# CAN_Interface.net
KiCad netlist of a schematic drawn in Altium Designer
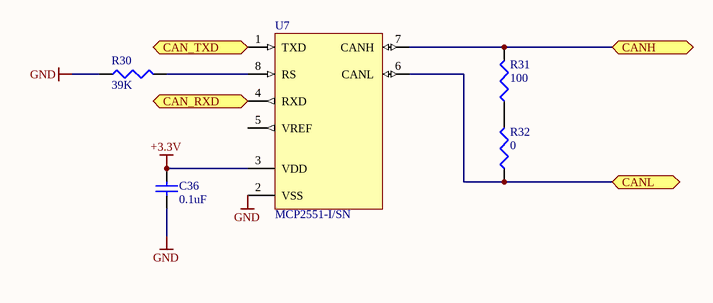
[diagram p0: CAN Interface.SchDoc]

(export (version "E")
  (design (tool "Eeschema 10.0.6"))
  (components
    (comp (ref "C36")
      (value "0.1uF")
      (footprint "2012[0805]")
      (description "Ceramic Chip Capacitor - Standard")
      (fields (field (name "PUBLISHER") "Altium Limited"))
      (libsource (lib "ResAndCaps") (part "C0805"))
    )
    (comp (ref "R30")
      (value "39K")
      (footprint "R2012[0805]")
      (description "R0805")
      (fields (field (name "PUBLISHER") "Altium Limited"))
      (libsource (lib "ResAndCaps") (part "R0805"))
    )
    (comp (ref "R31")
      (value "100")
      (footprint "R2012[0805]")
      (description "R0805")
      (fields (field (name "PUBLISHER") "Altium Limited"))
      (libsource (lib "ResAndCaps") (part "R0805"))
    )
    (comp (ref "R32")
      (value "0")
      (footprint "R2012[0805]")
      (description "R0805")
      (fields (field (name "PUBLISHER") "Altium Limited"))
      (libsource (lib "ResAndCaps") (part "R0805"))
    )
    (comp (ref "U7")
      (value "MCP2551-I/SN")
      (footprint "SOIC-SN8_N")
      (description "High-Speed CAN Transceiver, 8-Pin SOIC, Industrial Temperature")
      (libsource (lib "Microchip Interface") (part "MCP2551-I/SN"))
    )
  )
  (nets
    (net (code "1") (name "+3.3V") (class "Default")
      (node (ref "C36") (pin "2") (pinfunction "2_2") (pintype "passive"))
      (node (ref "U7") (pin "3") (pinfunction "VDD_3") (pintype "power_in"))
    )
    (net (code "2") (name "/CANH") (class "Default")
      (node (ref "R31") (pin "2") (pinfunction "2_2") (pintype "passive"))
      (node (ref "U7") (pin "7") (pinfunction "CANH_7") (pintype "bidirectional"))
    )
    (net (code "3") (name "/CANL") (class "Default")
      (node (ref "R32") (pin "1") (pinfunction "1_1") (pintype "passive"))
      (node (ref "U7") (pin "6") (pinfunction "CANL_6") (pintype "bidirectional"))
    )
    (net (code "4") (name "/CAN_RXD") (class "Default")
      (node (ref "U7") (pin "4") (pinfunction "RXD_4") (pintype "output"))
    )
    (net (code "5") (name "/CAN_TXD") (class "Default")
      (node (ref "U7") (pin "1") (pinfunction "TXD_1") (pintype "input"))
    )
    (net (code "6") (name "GND") (class "Default")
      (node (ref "C36") (pin "1") (pinfunction "1_1") (pintype "passive"))
      (node (ref "R30") (pin "1") (pinfunction "1_1") (pintype "passive"))
      (node (ref "U7") (pin "2") (pinfunction "VSS_2") (pintype "power_in"))
    )
    (net (code "7") (name "Net-(R31-Pad1)") (class "Default")
      (node (ref "R31") (pin "1") (pinfunction "1_1") (pintype "passive"))
      (node (ref "R32") (pin "2") (pinfunction "2_2") (pintype "passive"))
    )
    (net (code "8") (name "Net-(U7-RS)") (class "Default")
      (node (ref "R30") (pin "2") (pinfunction "2_2") (pintype "passive"))
      (node (ref "U7") (pin "8") (pinfunction "RS_8") (pintype "input"))
    )
    (net (code "9") (name "unconnected-(U7-VREF-Pad5)") (class "Default")
      (node (ref "U7") (pin "5") (pinfunction "VREF_5") (pintype "output"))
    )
  )
)
